# Versorgungsspannung.net
KiCad netlist of a schematic drawn in Altium Designer
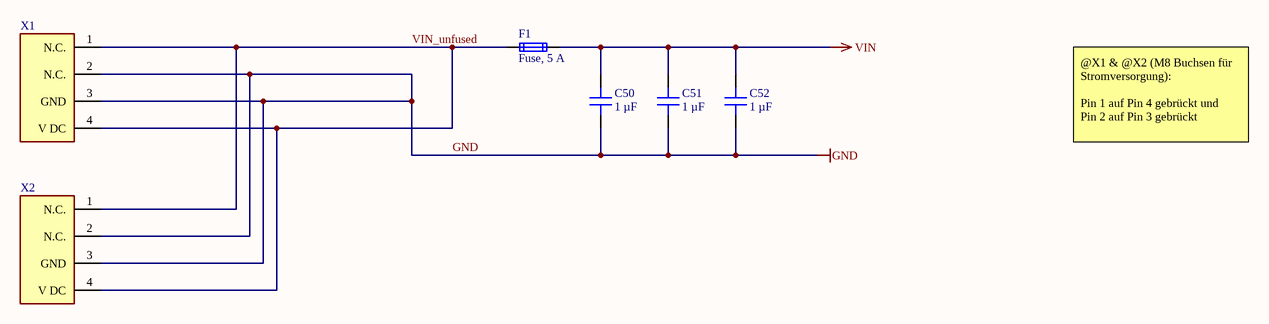
[diagram p0: Versorgungsspannung.SchDoc]

(export (version "E")
  (design (tool "Eeschema 10.0.6"))
  (components
    (comp (ref "C50")
      (value "1 µF")
      (footprint "C_0603")
      (description "50V 1uF X5R ±10% 0603  Multilayer Ceramic Capacitors MLCC - SMD/SMT ROHS")
      (fields
        (field (name "MANUFACTURER") "Samsung Electro-Mechanics")
        (field (name "MANUFACTURER PART NUMBER") "CL10A105KB8NNNC")
        (field (name "CREATED FROM") "MGremer")
      )
      (libsource (lib "user") (part "Capacitor"))
    )
    (comp (ref "C51")
      (value "1 µF")
      (footprint "C_0603")
      (description "50V 1uF X5R ±10% 0603  Multilayer Ceramic Capacitors MLCC - SMD/SMT ROHS")
      (fields
        (field (name "MANUFACTURER") "Samsung Electro-Mechanics")
        (field (name "MANUFACTURER PART NUMBER") "CL10A105KB8NNNC")
        (field (name "CREATED FROM") "MGremer")
      )
      (libsource (lib "user") (part "Capacitor"))
    )
    (comp (ref "C52")
      (value "1 µF")
      (footprint "C_0603")
      (description "50V 1uF X5R ±10% 0603  Multilayer Ceramic Capacitors MLCC - SMD/SMT ROHS")
      (fields
        (field (name "MANUFACTURER") "Samsung Electro-Mechanics")
        (field (name "MANUFACTURER PART NUMBER") "CL10A105KB8NNNC")
        (field (name "CREATED FROM") "MGremer")
      )
      (libsource (lib "user") (part "Capacitor"))
    )
    (comp (ref "F1")
      (value "Fuse, 5 A")
      (footprint "0154xxx")
      (description "Fuse OMNI BLOK 154")
      (fields
        (field (name "MANUFACTURER PART NUMBER") "0154005.DR")
        (field (name "MANUFACTURER") "Littlefuse")
        (field (name "CREATED FROM") "MGremer")
      )
      (libsource (lib "user") (part "Polyswitch"))
    )
    (comp (ref "X1")
      (value "CAZN_M12-P4A-GPL_M12")
      (footprint "CAZN_M12-P4A-GPL_M12")
      (fields
        (field (name "MANUFACTURER") "CAZN")
        (field (name "LCSC PART NUMBER") "C19108992")
        (field (name "CREATED FROM") "TGaupp")
      )
      (libsource (lib "user") (part "CAZN_M12-P4A-GPL_M12"))
    )
    (comp (ref "X2")
      (value "CAZN_M12-P4A-GPL_M12")
      (footprint "CAZN_M12-P4A-GPL_M12")
      (fields
        (field (name "MANUFACTURER") "CAZN")
        (field (name "LCSC PART NUMBER") "C19108992")
        (field (name "CREATED FROM") "TGaupp")
      )
      (libsource (lib "user") (part "CAZN_M12-P4A-GPL_M12"))
    )
  )
  (nets
    (net (code "1") (name "/VIN_unfused") (class "Default")
      (node (ref "F1") (pin "1") (pinfunction "1_1") (pintype "passive"))
      (node (ref "X1") (pin "1") (pinfunction "N.C._1") (pintype "passive"))
      (node (ref "X1") (pin "4") (pinfunction "V_DC_4") (pintype "power_in"))
      (node (ref "X2") (pin "1") (pinfunction "N.C._1") (pintype "passive"))
      (node (ref "X2") (pin "4") (pinfunction "V_DC_4") (pintype "power_in"))
    )
    (net (code "2") (name "GND") (class "Default")
      (node (ref "C50") (pin "2") (pinfunction "2_2") (pintype "passive"))
      (node (ref "C51") (pin "2") (pinfunction "2_2") (pintype "passive"))
      (node (ref "C52") (pin "2") (pinfunction "2_2") (pintype "passive"))
      (node (ref "X1") (pin "2") (pinfunction "N.C._2") (pintype "passive"))
      (node (ref "X1") (pin "3") (pinfunction "GND_3") (pintype "power_in"))
      (node (ref "X2") (pin "2") (pinfunction "N.C._2") (pintype "passive"))
      (node (ref "X2") (pin "3") (pinfunction "GND_3") (pintype "power_in"))
    )
    (net (code "3") (name "VIN") (class "Default")
      (node (ref "C50") (pin "1") (pinfunction "1_1") (pintype "passive"))
      (node (ref "C51") (pin "1") (pinfunction "1_1") (pintype "passive"))
      (node (ref "C52") (pin "1") (pinfunction "1_1") (pintype "passive"))
      (node (ref "F1") (pin "2") (pinfunction "2_2") (pintype "passive"))
    )
  )
)
